# js220_evk1.net
KiCad netlist of a schematic drawn in EAGLE
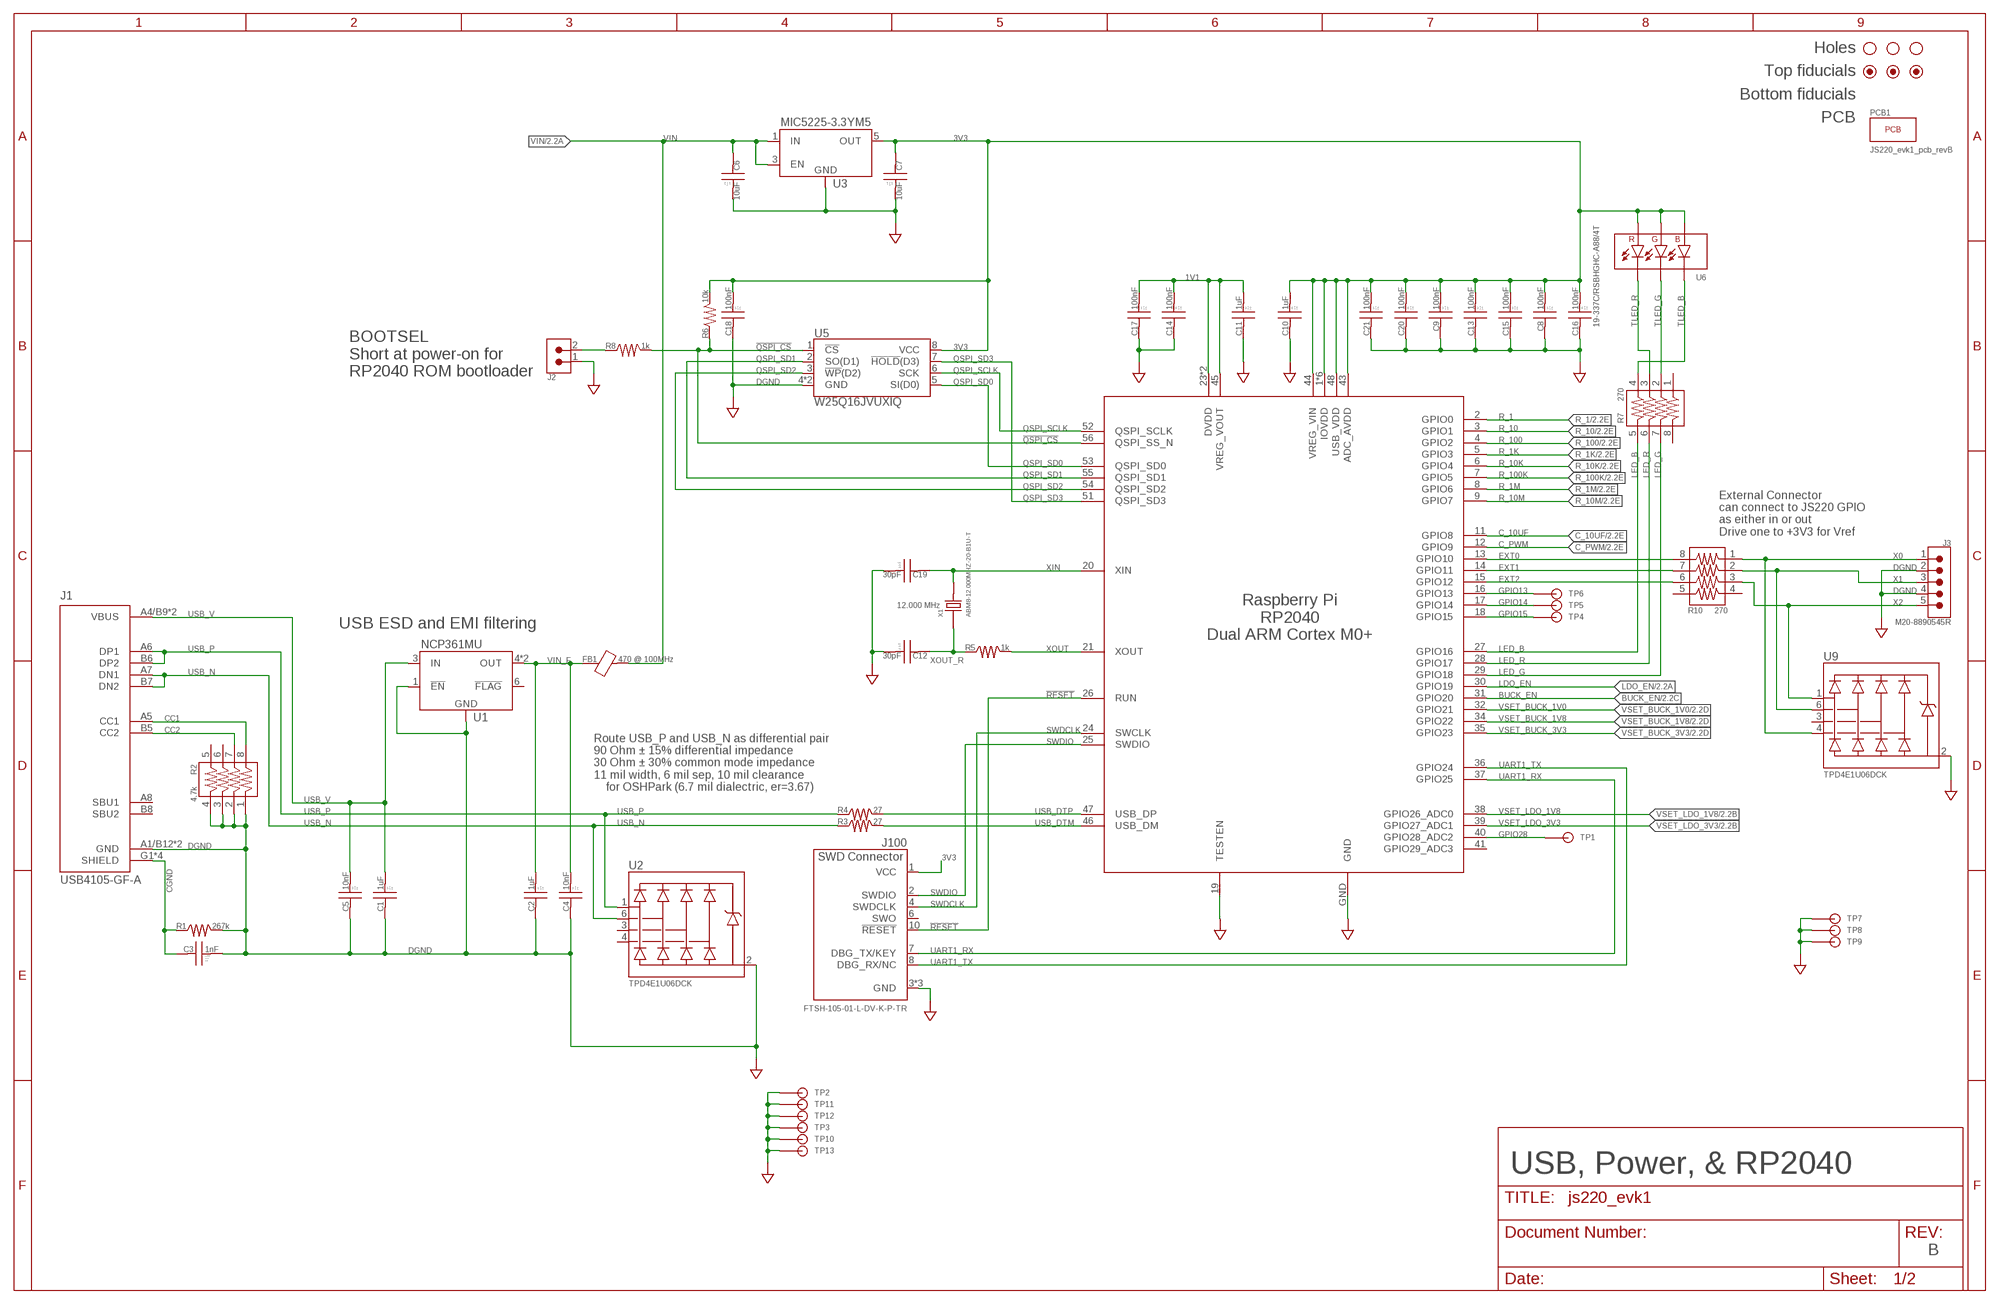
[diagram p0: schematic, sheet 1]
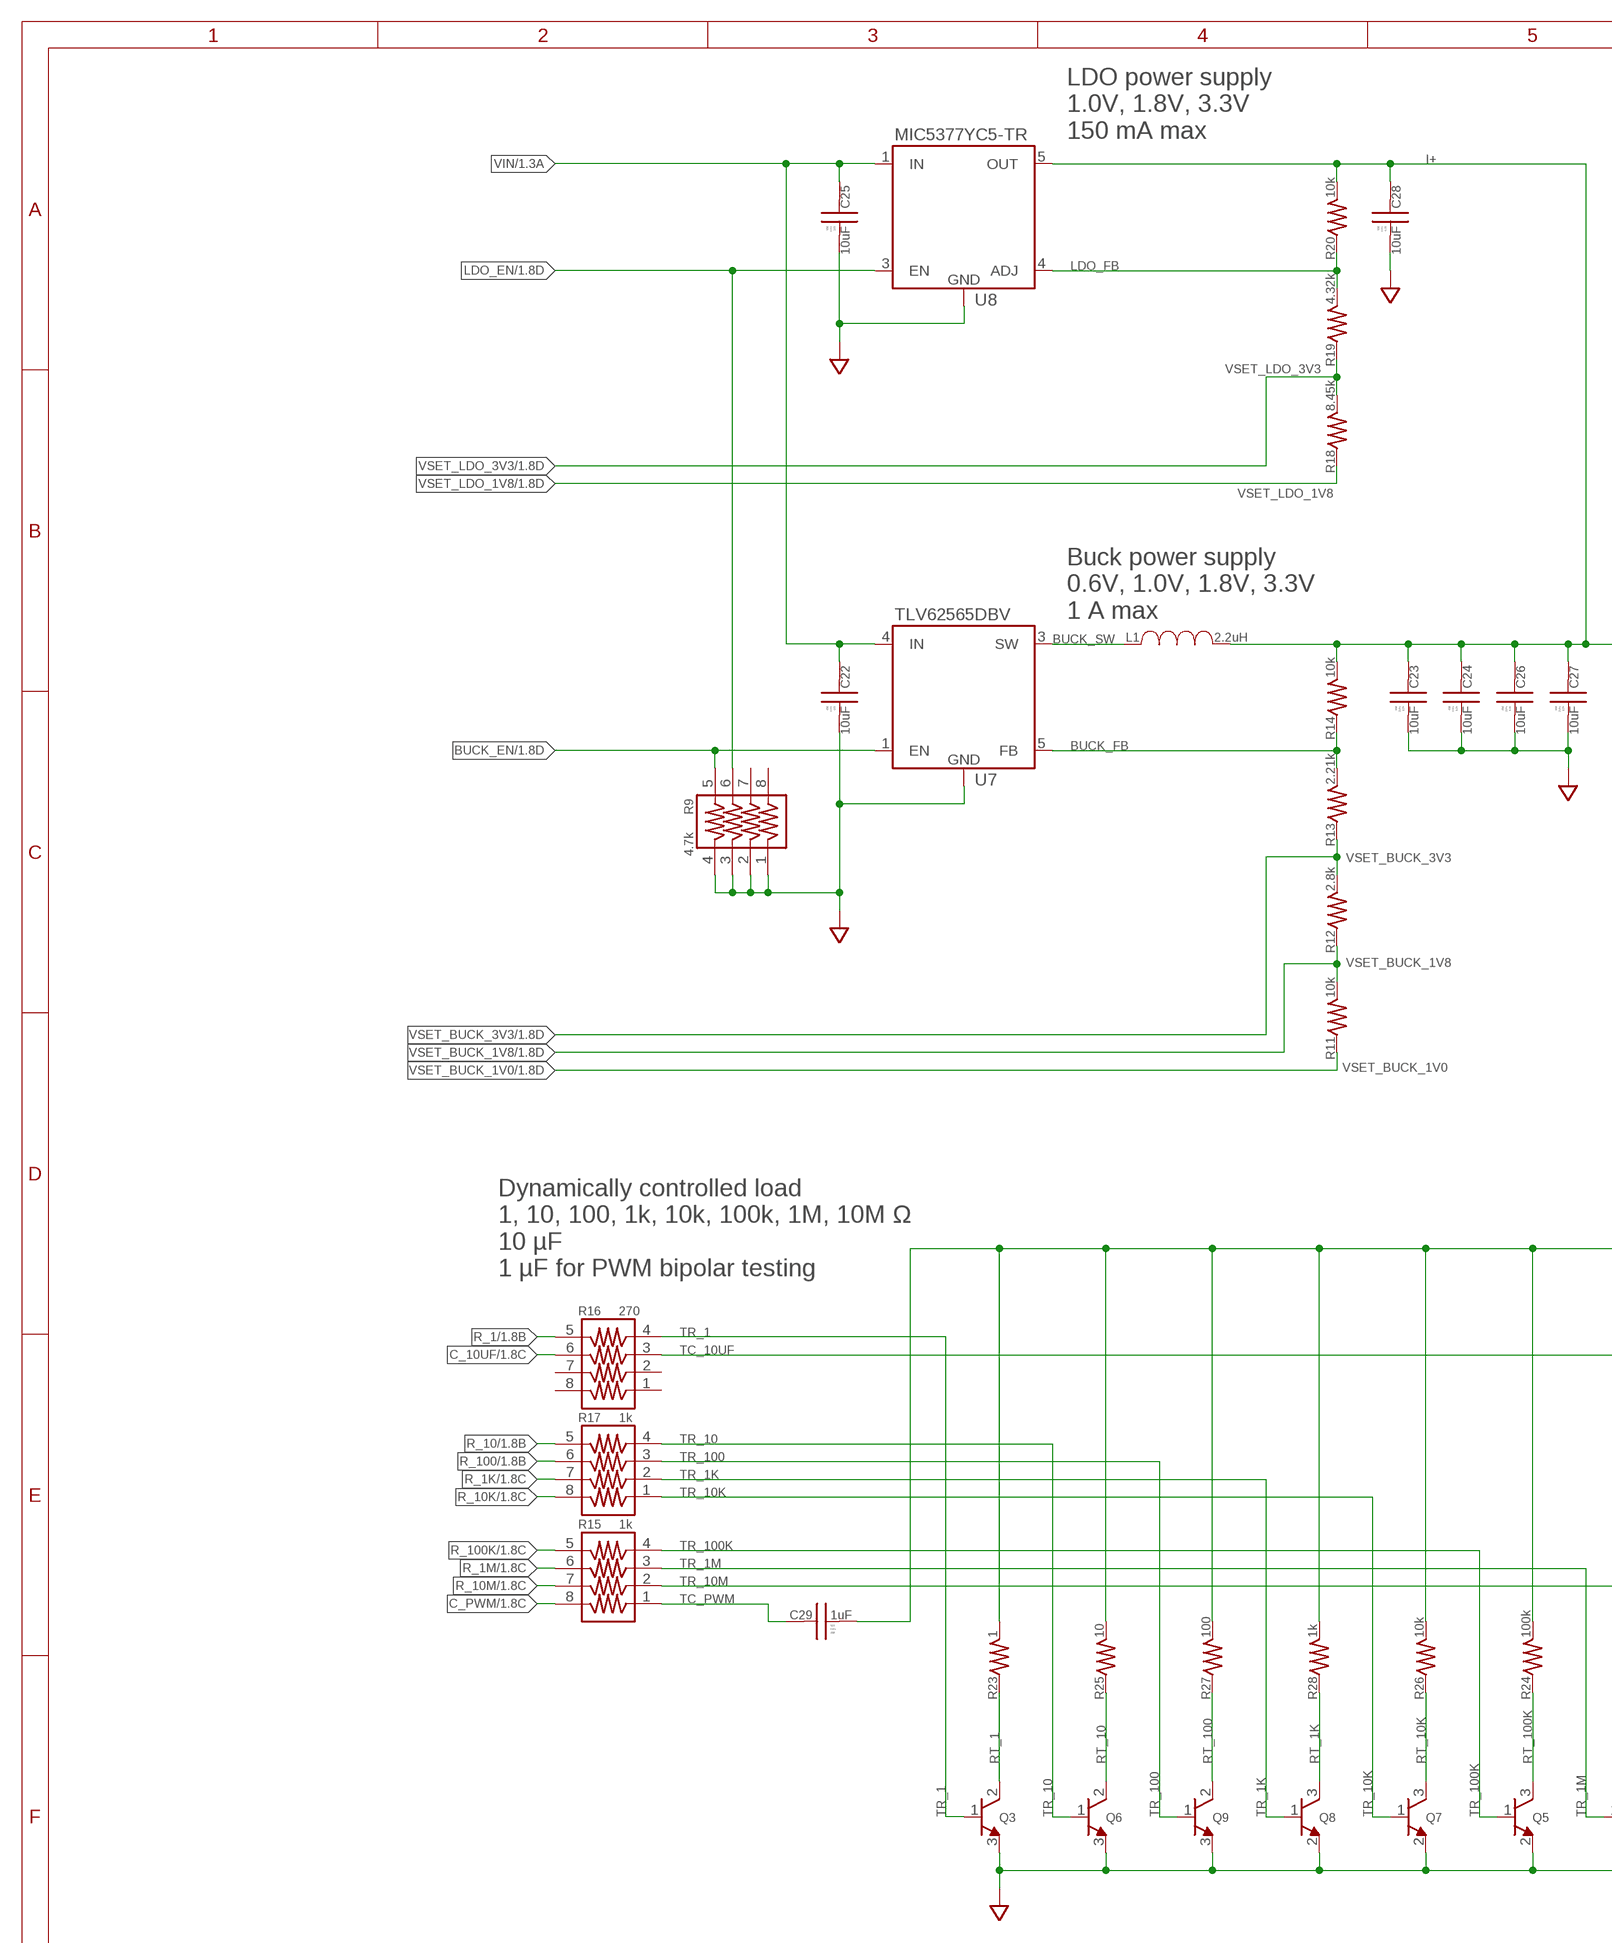
[diagram p1: schematic, sheet 2, part 1 of 2]
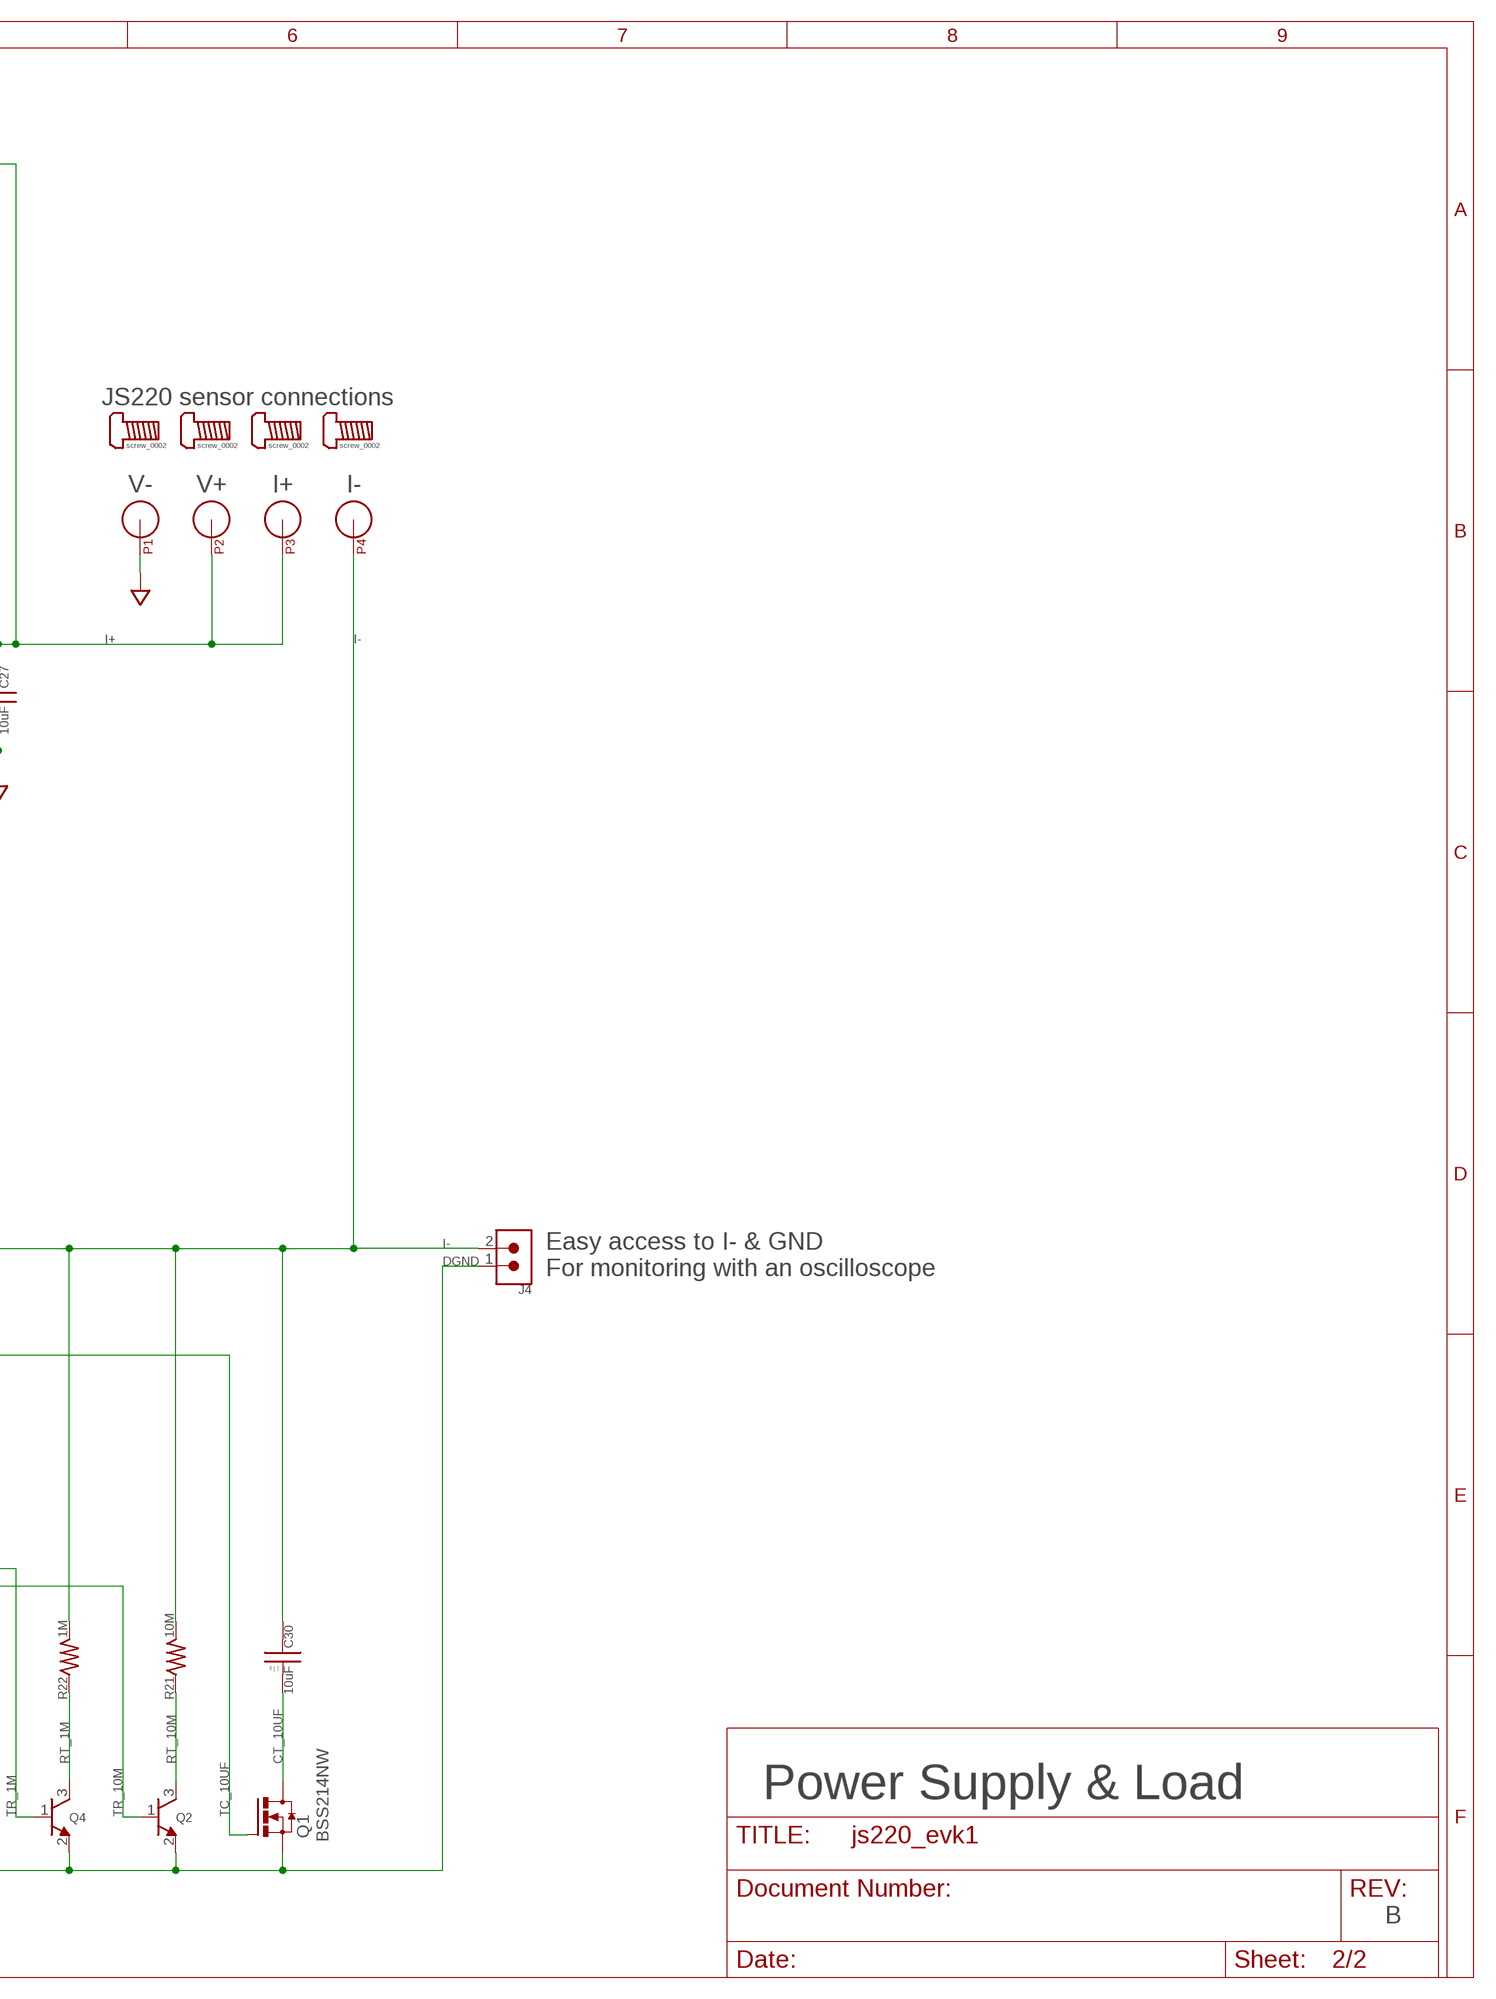
[diagram p2: schematic, sheet 2, part 2 of 2]

(export (version "E")
  (design (tool "Eeschema 10.0.6"))
  (components
    (comp (ref "C1")
      (value "1uF")
      (footprint "eagle-import:0603")
      (fields
        (field (name "DIELECTRIC") "X5R")
        (field (name "TOLERANCE") "20%")
        (field (name "VOLTAGE") "50V")
      )
      (libsource (lib "eagle-import") (part "CAP_0603"))
    )
    (comp (ref "C2")
      (value "1uF")
      (footprint "eagle-import:0603")
      (fields
        (field (name "DIELECTRIC") "X5R")
        (field (name "TOLERANCE") "20%")
        (field (name "VOLTAGE") "50V")
      )
      (libsource (lib "eagle-import") (part "CAP_0603"))
    )
    (comp (ref "C3")
      (value "1nF")
      (footprint "eagle-import:0805")
      (fields
        (field (name "DIELECTRIC") "X5R")
        (field (name "TOLERANCE") "20%")
        (field (name "VOLTAGE") "1000V")
      )
      (libsource (lib "eagle-import") (part "CAP_0805"))
    )
    (comp (ref "C4")
      (value "10nF")
      (footprint "eagle-import:0402")
      (fields
        (field (name "DIELECTRIC") "X7R")
        (field (name "TOLERANCE") "10%")
        (field (name "VOLTAGE") "50V")
      )
      (libsource (lib "eagle-import") (part "CAP_0402"))
    )
    (comp (ref "C5")
      (value "10nF")
      (footprint "eagle-import:0402")
      (fields
        (field (name "DIELECTRIC") "X7R")
        (field (name "TOLERANCE") "10%")
        (field (name "VOLTAGE") "50V")
      )
      (libsource (lib "eagle-import") (part "CAP_0402"))
    )
    (comp (ref "C6")
      (value "10uF")
      (footprint "eagle-import:1206")
      (fields
        (field (name "DIELECTRIC") "X5R")
        (field (name "TOLERANCE") "20%")
        (field (name "VOLTAGE") "10V")
      )
      (libsource (lib "eagle-import") (part "CAP_1206"))
    )
    (comp (ref "C7")
      (value "10uF")
      (footprint "eagle-import:0805")
      (fields
        (field (name "DIELECTRIC") "X5R")
        (field (name "TOLERANCE") "20%")
        (field (name "VOLTAGE") "6.3V")
      )
      (libsource (lib "eagle-import") (part "CAP_0805"))
    )
    (comp (ref "C8")
      (value "100nF")
      (footprint "eagle-import:0402")
      (fields
        (field (name "DIELECTRIC") "X7R")
        (field (name "TOLERANCE") "10%")
        (field (name "VOLTAGE") "50V")
      )
      (libsource (lib "eagle-import") (part "CAP_0402"))
    )
    (comp (ref "C9")
      (value "100nF")
      (footprint "eagle-import:0402")
      (fields
        (field (name "DIELECTRIC") "X7R")
        (field (name "TOLERANCE") "10%")
        (field (name "VOLTAGE") "50V")
      )
      (libsource (lib "eagle-import") (part "CAP_0402"))
    )
    (comp (ref "C10")
      (value "1uF")
      (footprint "eagle-import:0603")
      (fields
        (field (name "DIELECTRIC") "X5R")
        (field (name "TOLERANCE") "20%")
        (field (name "VOLTAGE") "50V")
      )
      (libsource (lib "eagle-import") (part "CAP_0603"))
    )
    (comp (ref "C11")
      (value "1uF")
      (footprint "eagle-import:0603")
      (fields
        (field (name "DIELECTRIC") "X5R")
        (field (name "TOLERANCE") "20%")
        (field (name "VOLTAGE") "50V")
      )
      (libsource (lib "eagle-import") (part "CAP_0603"))
    )
    (comp (ref "C12")
      (value "30pF")
      (footprint "eagle-import:0402")
      (fields
        (field (name "DIELECTRIC") "C0G")
        (field (name "TOLERANCE") "5%")
        (field (name "VOLTAGE") "50V")
      )
      (libsource (lib "eagle-import") (part "CAP_0402"))
    )
    (comp (ref "C13")
      (value "100nF")
      (footprint "eagle-import:0402")
      (fields
        (field (name "DIELECTRIC") "X7R")
        (field (name "TOLERANCE") "10%")
        (field (name "VOLTAGE") "50V")
      )
      (libsource (lib "eagle-import") (part "CAP_0402"))
    )
    (comp (ref "C14")
      (value "100nF")
      (footprint "eagle-import:0402")
      (fields
        (field (name "DIELECTRIC") "X7R")
        (field (name "TOLERANCE") "10%")
        (field (name "VOLTAGE") "50V")
      )
      (libsource (lib "eagle-import") (part "CAP_0402"))
    )
    (comp (ref "C15")
      (value "100nF")
      (footprint "eagle-import:0402")
      (fields
        (field (name "DIELECTRIC") "X7R")
        (field (name "TOLERANCE") "10%")
        (field (name "VOLTAGE") "50V")
      )
      (libsource (lib "eagle-import") (part "CAP_0402"))
    )
    (comp (ref "C16")
      (value "100nF")
      (footprint "eagle-import:0402")
      (fields
        (field (name "DIELECTRIC") "X7R")
        (field (name "TOLERANCE") "10%")
        (field (name "VOLTAGE") "50V")
      )
      (libsource (lib "eagle-import") (part "CAP_0402"))
    )
    (comp (ref "C17")
      (value "100nF")
      (footprint "eagle-import:0402")
      (fields
        (field (name "DIELECTRIC") "X7R")
        (field (name "TOLERANCE") "10%")
        (field (name "VOLTAGE") "50V")
      )
      (libsource (lib "eagle-import") (part "CAP_0402"))
    )
    (comp (ref "C18")
      (value "100nF")
      (footprint "eagle-import:0402")
      (fields
        (field (name "DIELECTRIC") "X7R")
        (field (name "TOLERANCE") "10%")
        (field (name "VOLTAGE") "50V")
      )
      (libsource (lib "eagle-import") (part "CAP_0402"))
    )
    (comp (ref "C19")
      (value "30pF")
      (footprint "eagle-import:0402")
      (fields
        (field (name "DIELECTRIC") "C0G")
        (field (name "TOLERANCE") "5%")
        (field (name "VOLTAGE") "50V")
      )
      (libsource (lib "eagle-import") (part "CAP_0402"))
    )
    (comp (ref "C20")
      (value "100nF")
      (footprint "eagle-import:0402")
      (fields
        (field (name "DIELECTRIC") "X7R")
        (field (name "TOLERANCE") "10%")
        (field (name "VOLTAGE") "50V")
      )
      (libsource (lib "eagle-import") (part "CAP_0402"))
    )
    (comp (ref "C21")
      (value "100nF")
      (footprint "eagle-import:0402")
      (fields
        (field (name "DIELECTRIC") "X7R")
        (field (name "TOLERANCE") "10%")
        (field (name "VOLTAGE") "50V")
      )
      (libsource (lib "eagle-import") (part "CAP_0402"))
    )
    (comp (ref "FB1")
      (value "470 @ 100MHz")
      (footprint "eagle-import:0603")
      (libsource (lib "eagle-import") (part "FERRITE_BEAD_0603"))
    )
    (comp (ref "FD1")
      (value "DNI")
      (footprint "eagle-import:FIDUCIAL_1MM_2MM")
      (libsource (lib "eagle-import") (part "FIDUCIAL_1MM"))
    )
    (comp (ref "FD2")
      (value "DNI")
      (footprint "eagle-import:FIDUCIAL_1MM_2MM")
      (libsource (lib "eagle-import") (part "FIDUCIAL_1MM"))
    )
    (comp (ref "FD3")
      (value "DNI")
      (footprint "eagle-import:FIDUCIAL_1MM_2MM")
      (libsource (lib "eagle-import") (part "FIDUCIAL_1MM"))
    )
    (comp (ref "H1")
      (value "STAND-OFFTIGHT")
      (footprint "eagle-import:STAND-OFF-TIGHT")
      (libsource (lib "eagle-import") (part "STAND-OFFTIGHT"))
    )
    (comp (ref "H2")
      (value "STAND-OFFTIGHT")
      (footprint "eagle-import:STAND-OFF-TIGHT")
      (libsource (lib "eagle-import") (part "STAND-OFFTIGHT"))
    )
    (comp (ref "H3")
      (value "STAND-OFFTIGHT")
      (footprint "eagle-import:STAND-OFF-TIGHT")
      (libsource (lib "eagle-import") (part "STAND-OFFTIGHT"))
    )
    (comp (ref "J1")
      (value "USB4105-GF-A")
      (footprint "eagle-import:GCT_USB4105_REVA")
      (fields
        (field (name "DIGI-KEY_PART_NUMBER") "2073-USB4105-GF-ACT-ND")
        (field (name "MF") "Global Connector Technology")
        (field (name "MP") "USB4105")
      )
      (libsource (lib "eagle-import") (part "USB4105_REVA"))
    )
    (comp (ref "J2")
      (value "CONN_0.1_2X1")
      (footprint "eagle-import:CONN_0.1_2X1_M")
      (libsource (lib "eagle-import") (part "CONN_0.1_2X1"))
    )
    (comp (ref "J3")
      (value "M20-8890545R")
      (footprint "eagle-import:CONN_0.1_5X1_MSR")
      (libsource (lib "eagle-import") (part "CONN_0.1_5X1_MSR"))
    )
    (comp (ref "J100")
      (value "FTSH-105-01-L-DV-K-P-TR")
      (footprint "eagle-import:CONN_0.050_5X2_M_SM")
      (libsource (lib "eagle-import") (part "ARM_SWD_10_0.05_2X10_S"))
    )
    (comp (ref "R1")
      (value "267k")
      (footprint "eagle-import:0402")
      (fields
        (field (name "TEMP_CO") "100 ppm/°C")
        (field (name "TOLERANCE") "1%")
        (field (name "WATTAGE") "0.062W")
      )
      (libsource (lib "eagle-import") (part "RESISTOR_0402"))
    )
    (comp (ref "R2")
      (value "4.7k")
      (footprint "eagle-import:0402X4")
      (fields (field (name "TOLERANCE") "5%"))
      (libsource (lib "eagle-import") (part "RESISTOR_4_0804"))
    )
    (comp (ref "R3")
      (value "27")
      (footprint "eagle-import:0402")
      (fields
        (field (name "TEMP_CO") "100 ppm/°C")
        (field (name "TOLERANCE") "1%")
        (field (name "WATTAGE") "0.062W")
      )
      (libsource (lib "eagle-import") (part "RESISTOR_0402"))
    )
    (comp (ref "R4")
      (value "27")
      (footprint "eagle-import:0402")
      (fields
        (field (name "TEMP_CO") "100 ppm/°C")
        (field (name "TOLERANCE") "1%")
        (field (name "WATTAGE") "0.062W")
      )
      (libsource (lib "eagle-import") (part "RESISTOR_0402"))
    )
    (comp (ref "R5")
      (value "1k")
      (footprint "eagle-import:0402")
      (fields
        (field (name "TEMP_CO") "25 ppm/°C")
        (field (name "TOLERANCE") "0.1%")
        (field (name "WATTAGE") "0.062W")
      )
      (libsource (lib "eagle-import") (part "RESISTOR_0402"))
    )
    (comp (ref "R6")
      (value "10k")
      (footprint "eagle-import:0402")
      (fields
        (field (name "TEMP_CO") "25 ppm/°C")
        (field (name "TOLERANCE") "0.1%")
        (field (name "WATTAGE") "0.062W")
      )
      (libsource (lib "eagle-import") (part "RESISTOR_0402"))
    )
    (comp (ref "R7")
      (value "270")
      (footprint "eagle-import:0402X4")
      (fields (field (name "TOLERANCE") "5%"))
      (libsource (lib "eagle-import") (part "RESISTOR_4_0804"))
    )
    (comp (ref "R8")
      (value "1k")
      (footprint "eagle-import:0402")
      (fields
        (field (name "TEMP_CO") "25 ppm/°C")
        (field (name "TOLERANCE") "0.1%")
        (field (name "WATTAGE") "0.062W")
      )
      (libsource (lib "eagle-import") (part "RESISTOR_0402"))
    )
    (comp (ref "R10")
      (value "270")
      (footprint "eagle-import:0402X4")
      (fields (field (name "TOLERANCE") "5%"))
      (libsource (lib "eagle-import") (part "RESISTOR_4_0804"))
    )
    (comp (ref "TP1")
      (value "TPTP-PTH0.02")
      (footprint "eagle-import:TP-PTH0.02")
      (libsource (lib "eagle-import") (part "TPTP-PTH0.02"))
    )
    (comp (ref "TP2")
      (value "TPTP-PTH0.02")
      (footprint "eagle-import:TP-PTH0.02")
      (libsource (lib "eagle-import") (part "TPTP-PTH0.02"))
    )
    (comp (ref "TP3")
      (value "TPTP-PTH0.02")
      (footprint "eagle-import:TP-PTH0.02")
      (libsource (lib "eagle-import") (part "TPTP-PTH0.02"))
    )
    (comp (ref "TP4")
      (value "TPTP-PTH0.02")
      (footprint "eagle-import:TP-PTH0.02")
      (libsource (lib "eagle-import") (part "TPTP-PTH0.02"))
    )
    (comp (ref "TP5")
      (value "TPTP-PTH0.02")
      (footprint "eagle-import:TP-PTH0.02")
      (libsource (lib "eagle-import") (part "TPTP-PTH0.02"))
    )
    (comp (ref "TP6")
      (value "TPTP-PTH0.02")
      (footprint "eagle-import:TP-PTH0.02")
      (libsource (lib "eagle-import") (part "TPTP-PTH0.02"))
    )
    (comp (ref "TP7")
      (value "TPTP-PTH0.02")
      (footprint "eagle-import:TP-PTH0.02")
      (libsource (lib "eagle-import") (part "TPTP-PTH0.02"))
    )
    (comp (ref "TP8")
      (value "TPTP-PTH0.02")
      (footprint "eagle-import:TP-PTH0.02")
      (libsource (lib "eagle-import") (part "TPTP-PTH0.02"))
    )
    (comp (ref "TP9")
      (value "TPTP-PTH0.02")
      (footprint "eagle-import:TP-PTH0.02")
      (libsource (lib "eagle-import") (part "TPTP-PTH0.02"))
    )
    (comp (ref "TP10")
      (value "TPTP-PTH0.02")
      (footprint "eagle-import:TP-PTH0.02")
      (libsource (lib "eagle-import") (part "TPTP-PTH0.02"))
    )
    (comp (ref "TP11")
      (value "TPTP-PTH0.02")
      (footprint "eagle-import:TP-PTH0.02")
      (libsource (lib "eagle-import") (part "TPTP-PTH0.02"))
    )
    (comp (ref "TP12")
      (value "TPTP-PTH0.02")
      (footprint "eagle-import:TP-PTH0.02")
      (libsource (lib "eagle-import") (part "TPTP-PTH0.02"))
    )
    (comp (ref "TP13")
      (value "TPTP-PTH0.02")
      (footprint "eagle-import:TP-PTH0.02")
      (libsource (lib "eagle-import") (part "TPTP-PTH0.02"))
    )
    (comp (ref "U1")
      (value "NCP361MU")
      (footprint "eagle-import:UDFN-6")
      (fields (field (name "MPN") "NCP361MUTBG"))
      (libsource (lib "eagle-import") (part "NCP361MU"))
    )
    (comp (ref "U2")
      (value "TPD4E1U06DCK")
      (footprint "eagle-import:SC-70-6")
      (libsource (lib "eagle-import") (part "TVS_4UNI_DCK"))
    )
    (comp (ref "U3")
      (value "MIC5225-3.3YM5")
      (footprint "eagle-import:SOT23-5")
      (fields (field (name "MPN") "MIC5225-3.3YM5-TR"))
      (libsource (lib "eagle-import") (part "VREG_FIXED+_ENTPS70960DBV"))
    )
    (comp (ref "U4")
      (value "RP2040")
      (footprint "eagle-import:QFN-56G")
      (libsource (lib "eagle-import") (part "RP2040"))
    )
    (comp (ref "U5")
      (value "W25Q16JVUXIQ")
      (footprint "eagle-import:USON-8_2X3")
      (fields (field (name "MPN") "W25Q16JVUXIQ TR"))
      (libsource (lib "eagle-import") (part "FLASH_SERIAL8_USON8_2X3"))
    )
    (comp (ref "U6")
      (value "19-337C/RSBHGHC-A88/4T")
      (footprint "eagle-import:LED_RGB6_1.6X1.6")
      (libsource (lib "eagle-import") (part "LED_RGB6_1.6X1.6"))
    )
    (comp (ref "U9")
      (value "TPD4E1U06DCK")
      (footprint "eagle-import:SC-70-6")
      (libsource (lib "eagle-import") (part "TVS_4UNI_DCK"))
    )
    (comp (ref "X1")
      (value "ABM8-12.000MHZ-20-B1U-T")
      (footprint "eagle-import:XTAL4_3.2X2.5")
      (libsource (lib "eagle-import") (part "XTAL-2_XTAL4_3.2X2.5"))
    )
    (comp (ref "C22")
      (value "10uF")
      (footprint "eagle-import:1206")
      (fields
        (field (name "DIELECTRIC") "X5R")
        (field (name "TOLERANCE") "20%")
        (field (name "VOLTAGE") "10V")
      )
      (libsource (lib "eagle-import") (part "CAP_1206"))
    )
    (comp (ref "C23")
      (value "10uF")
      (footprint "eagle-import:0805")
      (fields
        (field (name "DIELECTRIC") "X5R")
        (field (name "TOLERANCE") "20%")
        (field (name "VOLTAGE") "6.3V")
      )
      (libsource (lib "eagle-import") (part "CAP_0805"))
    )
    (comp (ref "C24")
      (value "10uF")
      (footprint "eagle-import:0805")
      (fields
        (field (name "DIELECTRIC") "X5R")
        (field (name "TOLERANCE") "20%")
        (field (name "VOLTAGE") "6.3V")
      )
      (libsource (lib "eagle-import") (part "CAP_0805"))
    )
    (comp (ref "C25")
      (value "10uF")
      (footprint "eagle-import:1206")
      (fields
        (field (name "DIELECTRIC") "X5R")
        (field (name "TOLERANCE") "20%")
        (field (name "VOLTAGE") "10V")
      )
      (libsource (lib "eagle-import") (part "CAP_1206"))
    )
    (comp (ref "C26")
      (value "10uF")
      (footprint "eagle-import:0805")
      (fields
        (field (name "DIELECTRIC") "X5R")
        (field (name "TOLERANCE") "20%")
        (field (name "VOLTAGE") "6.3V")
      )
      (libsource (lib "eagle-import") (part "CAP_0805"))
    )
    (comp (ref "C27")
      (value "10uF")
      (footprint "eagle-import:0805")
      (fields
        (field (name "DIELECTRIC") "X5R")
        (field (name "TOLERANCE") "20%")
        (field (name "VOLTAGE") "6.3V")
      )
      (libsource (lib "eagle-import") (part "CAP_0805"))
    )
    (comp (ref "C28")
      (value "10uF")
      (footprint "eagle-import:0805")
      (fields
        (field (name "DIELECTRIC") "X5R")
        (field (name "TOLERANCE") "20%")
        (field (name "VOLTAGE") "6.3V")
      )
      (libsource (lib "eagle-import") (part "CAP_0805"))
    )
    (comp (ref "C29")
      (value "1uF")
      (footprint "eagle-import:0603")
      (fields
        (field (name "DIELECTRIC") "X5R")
        (field (name "TOLERANCE") "20%")
        (field (name "VOLTAGE") "50V")
      )
      (libsource (lib "eagle-import") (part "CAP_0603"))
    )
    (comp (ref "C30")
      (value "10uF")
      (footprint "eagle-import:0805")
      (fields
        (field (name "DIELECTRIC") "X5R")
        (field (name "TOLERANCE") "20%")
        (field (name "VOLTAGE") "6.3V")
      )
      (libsource (lib "eagle-import") (part "CAP_0805"))
    )
    (comp (ref "J4")
      (value "CONN_0.1_2X1")
      (footprint "eagle-import:CONN_0.1_2X1_M")
      (libsource (lib "eagle-import") (part "CONN_0.1_2X1"))
    )
    (comp (ref "L1")
      (value "2.2uH")
      (footprint "eagle-import:LPS4018")
      (fields (field (name "MPN") "NRS4018T2R2MDGJ"))
      (libsource (lib "eagle-import") (part "INDUCTOR_LPS4018"))
    )
    (comp (ref "P1")
      (value "P55-271F40N")
      (footprint "eagle-import:72918")
      (libsource (lib "eagle-import") (part "BANANA-PLUG72918"))
    )
    (comp (ref "P2")
      (value "P55-271F40N")
      (footprint "eagle-import:72918")
      (libsource (lib "eagle-import") (part "BANANA-PLUG72918"))
    )
    (comp (ref "P3")
      (value "P55-271F40N")
      (footprint "eagle-import:72918")
      (libsource (lib "eagle-import") (part "BANANA-PLUG72918"))
    )
    (comp (ref "P4")
      (value "P55-271F40N")
      (footprint "eagle-import:72918")
      (libsource (lib "eagle-import") (part "BANANA-PLUG72918"))
    )
    (comp (ref "Q1")
      (value "BSS214NW")
      (footprint "eagle-import:SOT323-3")
      (fields (field (name "MPN") "BSS214NWH6327XTSA1"))
      (libsource (lib "eagle-import") (part "MOSFET_N_SOT323_GSD"))
    )
    (comp (ref "Q2")
      (value "BC848W")
      (footprint "eagle-import:SOT323-3")
      (libsource (lib "eagle-import") (part "BJT_NPN_SOT323"))
    )
    (comp (ref "Q3")
      (value "PBSS4240X")
      (footprint "eagle-import:SOT-89")
      (libsource (lib "eagle-import") (part "BJT_NPN_SOT89"))
    )
    (comp (ref "Q4")
      (value "BC848W")
      (footprint "eagle-import:SOT323-3")
      (libsource (lib "eagle-import") (part "BJT_NPN_SOT323"))
    )
    (comp (ref "Q5")
      (value "BC848W")
      (footprint "eagle-import:SOT323-3")
      (libsource (lib "eagle-import") (part "BJT_NPN_SOT323"))
    )
    (comp (ref "Q6")
      (value "PBSS4240X")
      (footprint "eagle-import:SOT-89")
      (libsource (lib "eagle-import") (part "BJT_NPN_SOT89"))
    )
    (comp (ref "Q7")
      (value "BC848W")
      (footprint "eagle-import:SOT323-3")
      (libsource (lib "eagle-import") (part "BJT_NPN_SOT323"))
    )
    (comp (ref "Q8")
      (value "BC848W")
      (footprint "eagle-import:SOT323-3")
      (libsource (lib "eagle-import") (part "BJT_NPN_SOT323"))
    )
    (comp (ref "Q9")
      (value "PBSS4240X")
      (footprint "eagle-import:SOT-89")
      (libsource (lib "eagle-import") (part "BJT_NPN_SOT89"))
    )
    (comp (ref "R9")
      (value "4.7k")
      (footprint "eagle-import:0402X4")
      (fields (field (name "TOLERANCE") "5%"))
      (libsource (lib "eagle-import") (part "RESISTOR_4_0804"))
    )
    (comp (ref "R11")
      (value "10k")
      (footprint "eagle-import:0402")
      (fields
        (field (name "TEMP_CO") "25 ppm/°C")
        (field (name "TOLERANCE") "0.1%")
        (field (name "WATTAGE") "0.062W")
      )
      (libsource (lib "eagle-import") (part "RESISTOR_0402"))
    )
    (comp (ref "R12")
      (value "2.8k")
      (footprint "eagle-import:0402")
      (fields
        (field (name "TEMP_CO") "25 ppm/°C")
        (field (name "TOLERANCE") "0.1%")
        (field (name "WATTAGE") "0.062W")
      )
      (libsource (lib "eagle-import") (part "RESISTOR_0402"))
    )
    (comp (ref "R13")
      (value "2.21k")
      (footprint "eagle-import:0402")
      (fields
        (field (name "TEMP_CO") "25 ppm/°C")
        (field (name "TOLERANCE") "0.1%")
        (field (name "WATTAGE") "0.062W")
      )
      (libsource (lib "eagle-import") (part "RESISTOR_0402"))
    )
    (comp (ref "R14")
      (value "10k")
      (footprint "eagle-import:0402")
      (fields
        (field (name "TEMP_CO") "25 ppm/°C")
        (field (name "TOLERANCE") "0.1%")
        (field (name "WATTAGE") "0.062W")
      )
      (libsource (lib "eagle-import") (part "RESISTOR_0402"))
    )
    (comp (ref "R15")
      (value "1k")
      (footprint "eagle-import:0402X4")
      (fields (field (name "TOLERANCE") "5%"))
      (libsource (lib "eagle-import") (part "RESISTOR_4_0804"))
    )
    (comp (ref "R16")
      (value "270")
      (footprint "eagle-import:0402X4")
      (fields (field (name "TOLERANCE") "5%"))
      (libsource (lib "eagle-import") (part "RESISTOR_4_0804"))
    )
    (comp (ref "R17")
      (value "1k")
      (footprint "eagle-import:0402X4")
      (fields (field (name "TOLERANCE") "5%"))
      (libsource (lib "eagle-import") (part "RESISTOR_4_0804"))
    )
    (comp (ref "R18")
      (value "8.45k")
      (footprint "eagle-import:0402")
      (fields
        (field (name "TEMP_CO") "25 ppm/°C")
        (field (name "TOLERANCE") "1%")
        (field (name "WATTAGE") "0.062W")
      )
      (libsource (lib "eagle-import") (part "RESISTOR_0402"))
    )
    (comp (ref "R19")
      (value "4.32k")
      (footprint "eagle-import:0402")
      (fields
        (field (name "TEMP_CO") "25 ppm/°C")
        (field (name "TOLERANCE") "1%")
        (field (name "WATTAGE") "0.062W")
      )
      (libsource (lib "eagle-import") (part "RESISTOR_0402"))
    )
    (comp (ref "R20")
      (value "10k")
      (footprint "eagle-import:0402")
      (fields
        (field (name "TEMP_CO") "25 ppm/°C")
        (field (name "TOLERANCE") "0.1%")
        (field (name "WATTAGE") "0.062W")
      )
      (libsource (lib "eagle-import") (part "RESISTOR_0402"))
    )
    (comp (ref "R21")
      (value "10M")
      (footprint "eagle-import:0402")
      (fields
        (field (name "TEMP_CO") "100 ppm/°C")
        (field (name "TOLERANCE") "1%")
        (field (name "WATTAGE") "0.062W")
      )
      (libsource (lib "eagle-import") (part "RESISTOR_0402"))
    )
    (comp (ref "R22")
      (value "1M")
      (footprint "eagle-import:0402")
      (fields
        (field (name "TEMP_CO") "100 ppm/°C")
        (field (name "TOLERANCE") "1%")
        (field (name "WATTAGE") "0.062W")
      )
      (libsource (lib "eagle-import") (part "RESISTOR_0402"))
    )
    (comp (ref "R23")
      (value "1")
      (footprint "eagle-import:2512")
      (fields
        (field (name "TEMP_CO") "100 ppm/°C")
        (field (name "TOLERANCE") "1%")
        (field (name "WATTAGE") "2W")
      )
      (libsource (lib "eagle-import") (part "RESISTOR_2512"))
    )
    (comp (ref "R24")
      (value "100k")
      (footprint "eagle-import:0402")
      (fields
        (field (name "TEMP_CO") "25 ppm/°C")
        (field (name "TOLERANCE") "0.1%")
        (field (name "WATTAGE") "0.062W")
      )
      (libsource (lib "eagle-import") (part "RESISTOR_0402"))
    )
    (comp (ref "R25")
      (value "10")
      (footprint "eagle-import:2512")
      (fields
        (field (name "TEMP_CO") "100 ppm/°C")
        (field (name "TOLERANCE") "1%")
        (field (name "WATTAGE") "2W")
      )
      (libsource (lib "eagle-import") (part "RESISTOR_2512"))
    )
    (comp (ref "R26")
      (value "10k")
      (footprint "eagle-import:0402")
      (fields
        (field (name "TEMP_CO") "25 ppm/°C")
        (field (name "TOLERANCE") "0.1%")
        (field (name "WATTAGE") "0.062W")
      )
      (libsource (lib "eagle-import") (part "RESISTOR_0402"))
    )
    (comp (ref "R27")
      (value "100")
      (footprint "eagle-import:1206")
      (fields
        (field (name "TEMP_CO") "100 ppm/°C")
        (field (name "TOLERANCE") "1%")
        (field (name "WATTAGE") "0.5W")
      )
      (libsource (lib "eagle-import") (part "RESISTOR_1206"))
    )
    (comp (ref "R28")
      (value "1k")
      (footprint "eagle-import:0402")
      (fields
        (field (name "TEMP_CO") "25 ppm/°C")
        (field (name "TOLERANCE") "0.1%")
        (field (name "WATTAGE") "0.062W")
      )
      (libsource (lib "eagle-import") (part "RESISTOR_0402"))
    )
    (comp (ref "U7")
      (value "TLV62565DBV")
      (footprint "eagle-import:SOT23-5")
      (libsource (lib "eagle-import") (part "TLV62565DBV"))
    )
    (comp (ref "U8")
      (value "MIC5377YC5-TR")
      (footprint "eagle-import:SC-70-5")
      (fields (field (name "MPN") "MIC5377YC5-TR"))
      (libsource (lib "eagle-import") (part "VREG+_FB_EN_MIC5376-YC5"))
    )
  )
  (nets
    (net (code "1") (name "1V1") (class "Default")
      (node (ref "C11") (pin "2") (pinfunction "2_2") (pintype "bidirectional"))
      (node (ref "C14") (pin "2") (pinfunction "2_2") (pintype "bidirectional"))
      (node (ref "C17") (pin "2") (pinfunction "2_2") (pintype "bidirectional"))
      (node (ref "U4") (pin "23") (pinfunction "DVDD_23") (pintype "bidirectional"))
      (node (ref "U4") (pin "45") (pinfunction "VREG_VOUT_45") (pintype "bidirectional"))
      (node (ref "U4") (pin "50") (pinfunction "DVDD_50") (pintype "bidirectional"))
    )
    (net (code "2") (name "3V3") (class "Default")
      (node (ref "C10") (pin "2") (pinfunction "2_2") (pintype "bidirectional"))
      (node (ref "C13") (pin "2") (pinfunction "2_2") (pintype "bidirectional"))
      (node (ref "C15") (pin "2") (pinfunction "2_2") (pintype "bidirectional"))
      (node (ref "C16") (pin "2") (pinfunction "2_2") (pintype "bidirectional"))
      (node (ref "C18") (pin "2") (pinfunction "2_2") (pintype "bidirectional"))
      (node (ref "C20") (pin "2") (pinfunction "2_2") (pintype "bidirectional"))
      (node (ref "C21") (pin "2") (pinfunction "2_2") (pintype "bidirectional"))
      (node (ref "C7") (pin "1") (pinfunction "1_1") (pintype "bidirectional"))
      (node (ref "C8") (pin "2") (pinfunction "2_2") (pintype "bidirectional"))
      (node (ref "C9") (pin "2") (pinfunction "2_2") (pintype "bidirectional"))
      (node (ref "J100") (pin "1") (pinfunction "VCC_1") (pintype "bidirectional"))
      (node (ref "R6") (pin "2") (pinfunction "P$2_2") (pintype "bidirectional"))
      (node (ref "U3") (pin "5") (pinfunction "OUT_5") (pintype "bidirectional"))
      (node (ref "U4") (pin "1") (pinfunction "IOVDD_1") (pintype "bidirectional"))
      (node (ref "U4") (pin "10") (pinfunction "IOVDD_10") (pintype "bidirectional"))
      (node (ref "U4") (pin "22") (pinfunction "IOVDD_22") (pintype "bidirectional"))
      (node (ref "U4") (pin "33") (pinfunction "IOVDD_33") (pintype "bidirectional"))
      (node (ref "U4") (pin "42") (pinfunction "IOVDD_42") (pintype "bidirectional"))
      (node (ref "U4") (pin "43") (pinfunction "ADC_AVDD_43") (pintype "bidirectional"))
      (node (ref "U4") (pin "44") (pinfunction "VREG_VIN_44") (pintype "bidirectional"))
      (node (ref "U4") (pin "48") (pinfunction "USB_VDD_48") (pintype "bidirectional"))
      (node (ref "U4") (pin "49") (pinfunction "IOVDD_49") (pintype "bidirectional"))
      (node (ref "U5") (pin "8") (pinfunction "VCC_8") (pintype "bidirectional"))
      (node (ref "U6") (pin "2") (pinfunction "GREEN_ANODE+_2") (pintype "passive"))
      (node (ref "U6") (pin "4") (pinfunction "RED_ANODE+_4") (pintype "passive"))
      (node (ref "U6") (pin "6") (pinfunction "BLUE_ANODE+_6") (pintype "passive"))
    )
    (net (code "3") (name "BUCK_EN") (class "Default")
      (node (ref "R9") (pin "5") (pinfunction "4B_5") (pintype "bidirectional"))
      (node (ref "U4") (pin "31") (pinfunction "GPIO20_31") (pintype "bidirectional"))
      (node (ref "U7") (pin "1") (pinfunction "EN_1") (pintype "bidirectional"))
    )
    (net (code "4") (name "BUCK_FB") (class "Default")
      (node (ref "R13") (pin "2") (pinfunction "P$2_2") (pintype "bidirectional"))
      (node (ref "R14") (pin "1") (pinfunction "P$1_1") (pintype "bidirectional"))
      (node (ref "U7") (pin "5") (pinfunction "FB_5") (pintype "bidirectional"))
    )
    (net (code "5") (name "BUCK_SW") (class "Default")
      (node (ref "L1") (pin "1") (pinfunction "P$1_1") (pintype "bidirectional"))
      (node (ref "U7") (pin "3") (pinfunction "SW_3") (pintype "bidirectional"))
    )
    (net (code "6") (name "CC1") (class "Default")
      (node (ref "J1") (pin "A5") (pinfunction "CC1_A5") (pintype "bidirectional"))
      (node (ref "R2") (pin "8") (pinfunction "1B_8") (pintype "bidirectional"))
    )
    (net (code "7") (name "CC2") (class "Default")
      (node (ref "J1") (pin "B5") (pinfunction "CC2_B5") (pintype "bidirectional"))
      (node (ref "R2") (pin "7") (pinfunction "2B_7") (pintype "bidirectional"))
    )
    (net (code "8") (name "CGND") (class "Default")
      (node (ref "C3") (pin "1") (pinfunction "1_1") (pintype "bidirectional"))
      (node (ref "J1") (pin "G1") (pinfunction "SHIELD_G1") (pintype "power_in"))
      (node (ref "J1") (pin "G2") (pinfunction "SHIELD_G2") (pintype "power_in"))
      (node (ref "J1") (pin "G3") (pinfunction "SHIELD_G3") (pintype "power_in"))
      (node (ref "J1") (pin "G4") (pinfunction "SHIELD_G4") (pintype "power_in"))
      (node (ref "R1") (pin "1") (pinfunction "P$1_1") (pintype "bidirectional"))
    )
    (net (code "9") (name "CT_10UF") (class "Default")
      (node (ref "C30") (pin "2") (pinfunction "2_2") (pintype "bidirectional"))
      (node (ref "Q1") (pin "3") (pinfunction "D_3") (pintype "passive"))
    )
    (net (code "10") (name "C_10UF") (class "Default")
      (node (ref "R16") (pin "6") (pinfunction "3B_6") (pintype "bidirectional"))
      (node (ref "U4") (pin "11") (pinfunction "GPIO8_11") (pintype "bidirectional"))
    )
    (net (code "11") (name "C_PWM") (class "Default")
      (node (ref "R15") (pin "8") (pinfunction "1B_8") (pintype "bidirectional"))
      (node (ref "U4") (pin "12") (pinfunction "GPIO9_12") (pintype "bidirectional"))
    )
    (net (code "12") (name "DGND") (class "Default")
      (node (ref "C1") (pin "1") (pinfunction "1_1") (pintype "bidirectional"))
      (node (ref "C10") (pin "1") (pinfunction "1_1") (pintype "bidirectional"))
      (node (ref "C11") (pin "1") (pinfunction "1_1") (pintype "bidirectional"))
      (node (ref "C12") (pin "2") (pinfunction "2_2") (pintype "bidirectional"))
      (node (ref "C13") (pin "1") (pinfunction "1_1") (pintype "bidirectional"))
      (node (ref "C14") (pin "1") (pinfunction "1_1") (pintype "bidirectional"))
      (node (ref "C15") (pin "1") (pinfunction "1_1") (pintype "bidirectional"))
      (node (ref "C16") (pin "1") (pinfunction "1_1") (pintype "bidirectional"))
      (node (ref "C17") (pin "1") (pinfunction "1_1") (pintype "bidirectional"))
      (node (ref "C18") (pin "1") (pinfunction "1_1") (pintype "bidirectional"))
      (node (ref "C19") (pin "2") (pinfunction "2_2") (pintype "bidirectional"))
      (node (ref "C2") (pin "1") (pinfunction "1_1") (pintype "bidirectional"))
      (node (ref "C20") (pin "1") (pinfunction "1_1") (pintype "bidirectional"))
      (node (ref "C21") (pin "1") (pinfunction "1_1") (pintype "bidirectional"))
      (node (ref "C22") (pin "2") (pinfunction "2_2") (pintype "bidirectional"))
      (node (ref "C23") (pin "2") (pinfunction "2_2") (pintype "bidirectional"))
      (node (ref "C24") (pin "2") (pinfunction "2_2") (pintype "bidirectional"))
      (node (ref "C25") (pin "2") (pinfunction "2_2") (pintype "bidirectional"))
      (node (ref "C26") (pin "2") (pinfunction "2_2") (pintype "bidirectional"))
      (node (ref "C27") (pin "2") (pinfunction "2_2") (pintype "bidirectional"))
      (node (ref "C28") (pin "2") (pinfunction "2_2") (pintype "bidirectional"))
      (node (ref "C3") (pin "2") (pinfunction "2_2") (pintype "bidirectional"))
      (node (ref "C4") (pin "1") (pinfunction "1_1") (pintype "bidirectional"))
      (node (ref "C5") (pin "1") (pinfunction "1_1") (pintype "bidirectional"))
      (node (ref "C6") (pin "2") (pinfunction "2_2") (pintype "bidirectional"))
      (node (ref "C7") (pin "2") (pinfunction "2_2") (pintype "bidirectional"))
      (node (ref "C8") (pin "1") (pinfunction "1_1") (pintype "bidirectional"))
      (node (ref "C9") (pin "1") (pinfunction "1_1") (pintype "bidirectional"))
      (node (ref "J1") (pin "A1/B12") (pinfunction "GND_A1/B12") (pintype "power_in"))
      (node (ref "J1") (pin "B1/A12") (pinfunction "GND_B1/A12") (pintype "power_in"))
      (node (ref "J100") (pin "3") (pinfunction "GND_3") (pintype "bidirectional"))
      (node (ref "J100") (pin "5") (pinfunction "GND_5") (pintype "bidirectional"))
      (node (ref "J100") (pin "9") (pinfunction "GND_9") (pintype "bidirectional"))
      (node (ref "J2") (pin "1") (pinfunction "1_1") (pintype "bidirectional"))
      (node (ref "J3") (pin "2") (pinfunction "2_2") (pintype "bidirectional"))
      (node (ref "J3") (pin "4") (pinfunction "4_4") (pintype "bidirectional"))
      (node (ref "J4") (pin "1") (pinfunction "1_1") (pintype "bidirectional"))
      (node (ref "P1") (pin "1") (pinfunction "1_1") (pintype "bidirectional"))
      (node (ref "Q1") (pin "2") (pinfunction "S_2") (pintype "passive"))
      (node (ref "Q2") (pin "2") (pinfunction "EMITTER_2") (pintype "bidirectional"))
      (node (ref "Q3") (pin "3") (pinfunction "EMITTER_3") (pintype "bidirectional"))
      (node (ref "Q4") (pin "2") (pinfunction "EMITTER_2") (pintype "bidirectional"))
      (node (ref "Q5") (pin "2") (pinfunction "EMITTER_2") (pintype "bidirectional"))
      (node (ref "Q6") (pin "3") (pinfunction "EMITTER_3") (pintype "bidirectional"))
      (node (ref "Q7") (pin "2") (pinfunction "EMITTER_2") (pintype "bidirectional"))
      (node (ref "Q8") (pin "2") (pinfunction "EMITTER_2") (pintype "bidirectional"))
      (node (ref "Q9") (pin "3") (pinfunction "EMITTER_3") (pintype "bidirectional"))
      (node (ref "R1") (pin "2") (pinfunction "P$2_2") (pintype "bidirectional"))
      (node (ref "R2") (pin "1") (pinfunction "1A_1") (pintype "bidirectional"))
      (node (ref "R2") (pin "2") (pinfunction "2A_2") (pintype "bidirectional"))
      (node (ref "R2") (pin "3") (pinfunction "3A_3") (pintype "bidirectional"))
      (node (ref "R2") (pin "4") (pinfunction "4A_4") (pintype "bidirectional"))
      (node (ref "R9") (pin "1") (pinfunction "1A_1") (pintype "bidirectional"))
      (node (ref "R9") (pin "2") (pinfunction "2A_2") (pintype "bidirectional"))
      (node (ref "R9") (pin "3") (pinfunction "3A_3") (pintype "bidirectional"))
      (node (ref "R9") (pin "4") (pinfunction "4A_4") (pintype "bidirectional"))
      (node (ref "TP10") (pin "1") (pinfunction "TP_1") (pintype "bidirectional"))
      (node (ref "TP11") (pin "1") (pinfunction "TP_1") (pintype "bidirectional"))
      (node (ref "TP12") (pin "1") (pinfunction "TP_1") (pintype "bidirectional"))
      (node (ref "TP13") (pin "1") (pinfunction "TP_1") (pintype "bidirectional"))
      (node (ref "TP2") (pin "1") (pinfunction "TP_1") (pintype "bidirectional"))
      (node (ref "TP3") (pin "1") (pinfunction "TP_1") (pintype "bidirectional"))
      (node (ref "TP7") (pin "1") (pinfunction "TP_1") (pintype "bidirectional"))
      (node (ref "TP8") (pin "1") (pinfunction "TP_1") (pintype "bidirectional"))
      (node (ref "TP9") (pin "1") (pinfunction "TP_1") (pintype "bidirectional"))
      (node (ref "U1") (pin "1") (pinfunction "~{EN}_1") (pintype "bidirectional"))
      (node (ref "U1") (pin "2") (pinfunction "GND_2") (pintype "bidirectional"))
      (node (ref "U1") (pin "GND@PAD") (pinfunction "GND_GND@PAD") (pintype "bidirectional"))
      (node (ref "U2") (pin "2") (pinfunction "GND_2") (pintype "passive"))
      (node (ref "U3") (pin "2") (pinfunction "GND_2") (pintype "bidirectional"))
      (node (ref "U4") (pin "19") (pinfunction "TESTEN_19") (pintype "bidirectional"))
      (node (ref "U4") (pin "GND") (pinfunction "GND_GND") (pintype "bidirectional"))
      (node (ref "U5") (pin "4") (pinfunction "GND_4") (pintype "bidirectional"))
      (node (ref "U5") (pin "9") (pinfunction "GND_9") (pintype "bidirectional"))
      (node (ref "U7") (pin "2") (pinfunction "GND_2") (pintype "bidirectional"))
      (node (ref "U8") (pin "2") (pinfunction "GND_2") (pintype "bidirectional"))
      (node (ref "U9") (pin "2") (pinfunction "GND_2") (pintype "passive"))
    )
    (net (code "13") (name "EXT0") (class "Default")
      (node (ref "R10") (pin "8") (pinfunction "1B_8") (pintype "bidirectional"))
      (node (ref "U4") (pin "13") (pinfunction "GPIO10_13") (pintype "bidirectional"))
    )
    (net (code "14") (name "EXT1") (class "Default")
      (node (ref "R10") (pin "7") (pinfunction "2B_7") (pintype "bidirectional"))
      (node (ref "U4") (pin "14") (pinfunction "GPIO11_14") (pintype "bidirectional"))
    )
    (net (code "15") (name "EXT2") (class "Default")
      (node (ref "R10") (pin "6") (pinfunction "3B_6") (pintype "bidirectional"))
      (node (ref "U4") (pin "15") (pinfunction "GPIO12_15") (pintype "bidirectional"))
    )
    (net (code "16") (name "GPIO13") (class "Default")
      (node (ref "TP6") (pin "1") (pinfunction "TP_1") (pintype "bidirectional"))
      (node (ref "U4") (pin "16") (pinfunction "GPIO13_16") (pintype "bidirectional"))
    )
    (net (code "17") (name "GPIO14") (class "Default")
      (node (ref "TP5") (pin "1") (pinfunction "TP_1") (pintype "bidirectional"))
      (node (ref "U4") (pin "17") (pinfunction "GPIO14_17") (pintype "bidirectional"))
    )
    (net (code "18") (name "GPIO15") (class "Default")
      (node (ref "TP4") (pin "1") (pinfunction "TP_1") (pintype "bidirectional"))
      (node (ref "U4") (pin "18") (pinfunction "GPIO15_18") (pintype "bidirectional"))
    )
    (net (code "19") (name "GPIO28") (class "Default")
      (node (ref "TP1") (pin "1") (pinfunction "TP_1") (pintype "bidirectional"))
      (node (ref "U4") (pin "40") (pinfunction "GPIO28_ADC2_40") (pintype "bidirectional"))
    )
    (net (code "20") (name "I+") (class "Default")
      (node (ref "C23") (pin "1") (pinfunction "1_1") (pintype "bidirectional"))
      (node (ref "C24") (pin "1") (pinfunction "1_1") (pintype "bidirectional"))
      (node (ref "C26") (pin "1") (pinfunction "1_1") (pintype "bidirectional"))
      (node (ref "C27") (pin "1") (pinfunction "1_1") (pintype "bidirectional"))
      (node (ref "C28") (pin "1") (pinfunction "1_1") (pintype "bidirectional"))
      (node (ref "L1") (pin "2") (pinfunction "P$2_2") (pintype "bidirectional"))
      (node (ref "P2") (pin "1") (pinfunction "1_1") (pintype "bidirectional"))
      (node (ref "P3") (pin "1") (pinfunction "1_1") (pintype "bidirectional"))
      (node (ref "R14") (pin "2") (pinfunction "P$2_2") (pintype "bidirectional"))
      (node (ref "R20") (pin "2") (pinfunction "P$2_2") (pintype "bidirectional"))
      (node (ref "U8") (pin "5") (pinfunction "OUT_5") (pintype "bidirectional"))
    )
    (net (code "21") (name "I-") (class "Default")
      (node (ref "C29") (pin "2") (pinfunction "2_2") (pintype "bidirectional"))
      (node (ref "C30") (pin "1") (pinfunction "1_1") (pintype "bidirectional"))
      (node (ref "J4") (pin "2") (pinfunction "2_2") (pintype "bidirectional"))
      (node (ref "P4") (pin "1") (pinfunction "1_1") (pintype "bidirectional"))
      (node (ref "R21") (pin "2") (pinfunction "P$2_2") (pintype "bidirectional"))
      (node (ref "R22") (pin "2") (pinfunction "P$2_2") (pintype "bidirectional"))
      (node (ref "R23") (pin "2") (pinfunction "P$2_2") (pintype "bidirectional"))
      (node (ref "R24") (pin "2") (pinfunction "P$2_2") (pintype "bidirectional"))
      (node (ref "R25") (pin "2") (pinfunction "P$2_2") (pintype "bidirectional"))
      (node (ref "R26") (pin "2") (pinfunction "P$2_2") (pintype "bidirectional"))
      (node (ref "R27") (pin "2") (pinfunction "P$2_2") (pintype "bidirectional"))
      (node (ref "R28") (pin "2") (pinfunction "P$2_2") (pintype "bidirectional"))
    )
    (net (code "22") (name "LDO_EN") (class "Default")
      (node (ref "R9") (pin "6") (pinfunction "3B_6") (pintype "bidirectional"))
      (node (ref "U4") (pin "30") (pinfunction "GPIO19_30") (pintype "bidirectional"))
      (node (ref "U8") (pin "3") (pinfunction "EN_3") (pintype "bidirectional"))
    )
    (net (code "23") (name "LDO_FB") (class "Default")
      (node (ref "R19") (pin "2") (pinfunction "P$2_2") (pintype "bidirectional"))
      (node (ref "R20") (pin "1") (pinfunction "P$1_1") (pintype "bidirectional"))
      (node (ref "U8") (pin "4") (pinfunction "ADJ_4") (pintype "bidirectional"))
    )
    (net (code "24") (name "LED_B") (class "Default")
      (node (ref "R7") (pin "5") (pinfunction "4B_5") (pintype "bidirectional"))
      (node (ref "U4") (pin "27") (pinfunction "GPIO16_27") (pintype "bidirectional"))
    )
    (net (code "25") (name "LED_G") (class "Default")
      (node (ref "R7") (pin "7") (pinfunction "2B_7") (pintype "bidirectional"))
      (node (ref "U4") (pin "29") (pinfunction "GPIO18_29") (pintype "bidirectional"))
    )
    (net (code "26") (name "LED_R") (class "Default")
      (node (ref "R7") (pin "6") (pinfunction "3B_6") (pintype "bidirectional"))
      (node (ref "U4") (pin "28") (pinfunction "GPIO17_28") (pintype "bidirectional"))
    )
    (net (code "27") (name "Net-(R8-P$1)") (class "Default")
      (node (ref "J2") (pin "2") (pinfunction "2_2") (pintype "bidirectional"))
      (node (ref "R8") (pin "1") (pinfunction "P$1_1") (pintype "bidirectional"))
    )
    (net (code "28") (name "QSPI_SCLK") (class "Default")
      (node (ref "U4") (pin "52") (pinfunction "QSPI_SCLK_52") (pintype "bidirectional"))
      (node (ref "U5") (pin "6") (pinfunction "SCK_6") (pintype "bidirectional"))
    )
    (net (code "29") (name "QSPI_SD0") (class "Default")
      (node (ref "U4") (pin "53") (pinfunction "QSPI_SD0_53") (pintype "bidirectional"))
      (node (ref "U5") (pin "5") (pinfunction "SI(D0)_5") (pintype "bidirectional"))
    )
    (net (code "30") (name "QSPI_SD1") (class "Default")
      (node (ref "U4") (pin "55") (pinfunction "QSPI_SD1_55") (pintype "bidirectional"))
      (node (ref "U5") (pin "2") (pinfunction "SO(D1)_2") (pintype "bidirectional"))
    )
    (net (code "31") (name "QSPI_SD2") (class "Default")
      (node (ref "U4") (pin "54") (pinfunction "QSPI_SD2_54") (pintype "bidirectional"))
      (node (ref "U5") (pin "3") (pinfunction "~{WP}(D2)_3") (pintype "bidirectional"))
    )
    (net (code "32") (name "QSPI_SD3") (class "Default")
      (node (ref "U4") (pin "51") (pinfunction "QSPI_SD3_51") (pintype "bidirectional"))
      (node (ref "U5") (pin "7") (pinfunction "~{HOLD}(D3)_7") (pintype "bidirectional"))
    )
    (net (code "33") (name "RT_1") (class "Default")
      (node (ref "Q3") (pin "2") (pinfunction "COLLECTOR_2") (pintype "bidirectional"))
      (node (ref "R23") (pin "1") (pinfunction "P$1_1") (pintype "bidirectional"))
    )
    (net (code "34") (name "RT_1K") (class "Default")
      (node (ref "Q8") (pin "3") (pinfunction "COLLECTOR_3") (pintype "bidirectional"))
      (node (ref "R28") (pin "1") (pinfunction "P$1_1") (pintype "bidirectional"))
    )
    (net (code "35") (name "RT_1M") (class "Default")
      (node (ref "Q4") (pin "3") (pinfunction "COLLECTOR_3") (pintype "bidirectional"))
      (node (ref "R22") (pin "1") (pinfunction "P$1_1") (pintype "bidirectional"))
    )
    (net (code "36") (name "RT_10") (class "Default")
      (node (ref "Q6") (pin "2") (pinfunction "COLLECTOR_2") (pintype "bidirectional"))
      (node (ref "R25") (pin "1") (pinfunction "P$1_1") (pintype "bidirectional"))
    )
    (net (code "37") (name "RT_10K") (class "Default")
      (node (ref "Q7") (pin "3") (pinfunction "COLLECTOR_3") (pintype "bidirectional"))
      (node (ref "R26") (pin "1") (pinfunction "P$1_1") (pintype "bidirectional"))
    )
    (net (code "38") (name "RT_10M") (class "Default")
      (node (ref "Q2") (pin "3") (pinfunction "COLLECTOR_3") (pintype "bidirectional"))
      (node (ref "R21") (pin "1") (pinfunction "P$1_1") (pintype "bidirectional"))
    )
    (net (code "39") (name "RT_100") (class "Default")
      (node (ref "Q9") (pin "2") (pinfunction "COLLECTOR_2") (pintype "bidirectional"))
      (node (ref "R27") (pin "1") (pinfunction "P$1_1") (pintype "bidirectional"))
    )
    (net (code "40") (name "RT_100K") (class "Default")
      (node (ref "Q5") (pin "3") (pinfunction "COLLECTOR_3") (pintype "bidirectional"))
      (node (ref "R24") (pin "1") (pinfunction "P$1_1") (pintype "bidirectional"))
    )
    (net (code "41") (name "R_1") (class "Default")
      (node (ref "R16") (pin "5") (pinfunction "4B_5") (pintype "bidirectional"))
      (node (ref "U4") (pin "2") (pinfunction "GPIO0_2") (pintype "bidirectional"))
    )
    (net (code "42") (name "R_1K") (class "Default")
      (node (ref "R17") (pin "7") (pinfunction "2B_7") (pintype "bidirectional"))
      (node (ref "U4") (pin "5") (pinfunction "GPIO3_5") (pintype "bidirectional"))
    )
    (net (code "43") (name "R_1M") (class "Default")
      (node (ref "R15") (pin "6") (pinfunction "3B_6") (pintype "bidirectional"))
      (node (ref "U4") (pin "8") (pinfunction "GPIO6_8") (pintype "bidirectional"))
    )
    (net (code "44") (name "R_10") (class "Default")
      (node (ref "R17") (pin "5") (pinfunction "4B_5") (pintype "bidirectional"))
      (node (ref "U4") (pin "3") (pinfunction "GPIO1_3") (pintype "bidirectional"))
    )
    (net (code "45") (name "R_10K") (class "Default")
      (node (ref "R17") (pin "8") (pinfunction "1B_8") (pintype "bidirectional"))
      (node (ref "U4") (pin "6") (pinfunction "GPIO4_6") (pintype "bidirectional"))
    )
    (net (code "46") (name "R_10M") (class "Default")
      (node (ref "R15") (pin "7") (pinfunction "2B_7") (pintype "bidirectional"))
      (node (ref "U4") (pin "9") (pinfunction "GPIO7_9") (pintype "bidirectional"))
    )
    (net (code "47") (name "R_100") (class "Default")
      (node (ref "R17") (pin "6") (pinfunction "3B_6") (pintype "bidirectional"))
      (node (ref "U4") (pin "4") (pinfunction "GPIO2_4") (pintype "bidirectional"))
    )
    (net (code "48") (name "R_100K") (class "Default")
      (node (ref "R15") (pin "5") (pinfunction "4B_5") (pintype "bidirectional"))
      (node (ref "U4") (pin "7") (pinfunction "GPIO5_7") (pintype "bidirectional"))
    )
    (net (code "49") (name "SWDCLK") (class "Default")
      (node (ref "J100") (pin "4") (pinfunction "SWDCLK_4") (pintype "bidirectional"))
      (node (ref "U4") (pin "24") (pinfunction "SWCLK_24") (pintype "bidirectional"))
    )
    (net (code "50") (name "SWDIO") (class "Default")
      (node (ref "J100") (pin "2") (pinfunction "SWDIO_2") (pintype "bidirectional"))
      (node (ref "U4") (pin "25") (pinfunction "SWDIO_25") (pintype "bidirectional"))
    )
    (net (code "51") (name "TC_10UF") (class "Default")
      (node (ref "Q1") (pin "1") (pinfunction "G_1") (pintype "passive"))
      (node (ref "R16") (pin "3") (pinfunction "3A_3") (pintype "bidirectional"))
    )
    (net (code "52") (name "TC_PWM") (class "Default")
      (node (ref "C29") (pin "1") (pinfunction "1_1") (pintype "bidirectional"))
      (node (ref "R15") (pin "1") (pinfunction "1A_1") (pintype "bidirectional"))
    )
    (net (code "53") (name "TLED_B") (class "Default")
      (node (ref "R7") (pin "4") (pinfunction "4A_4") (pintype "bidirectional"))
      (node (ref "U6") (pin "5") (pinfunction "BLUE_CATHODE-_5") (pintype "passive"))
    )
    (net (code "54") (name "TLED_G") (class "Default")
      (node (ref "R7") (pin "2") (pinfunction "2A_2") (pintype "bidirectional"))
      (node (ref "U6") (pin "1") (pinfunction "GREEN_CATHODE-_1") (pintype "passive"))
    )
    (net (code "55") (name "TLED_R") (class "Default")
      (node (ref "R7") (pin "3") (pinfunction "3A_3") (pintype "bidirectional"))
      (node (ref "U6") (pin "3") (pinfunction "RED_CATHODE-_3") (pintype "passive"))
    )
    (net (code "56") (name "TR_1") (class "Default")
      (node (ref "Q3") (pin "1") (pinfunction "BASE_1") (pintype "bidirectional"))
      (node (ref "R16") (pin "4") (pinfunction "4A_4") (pintype "bidirectional"))
    )
    (net (code "57") (name "TR_1K") (class "Default")
      (node (ref "Q8") (pin "1") (pinfunction "BASE_1") (pintype "bidirectional"))
      (node (ref "R17") (pin "2") (pinfunction "2A_2") (pintype "bidirectional"))
    )
    (net (code "58") (name "TR_1M") (class "Default")
      (node (ref "Q4") (pin "1") (pinfunction "BASE_1") (pintype "bidirectional"))
      (node (ref "R15") (pin "3") (pinfunction "3A_3") (pintype "bidirectional"))
    )
    (net (code "59") (name "TR_10") (class "Default")
      (node (ref "Q6") (pin "1") (pinfunction "BASE_1") (pintype "bidirectional"))
      (node (ref "R17") (pin "4") (pinfunction "4A_4") (pintype "bidirectional"))
    )
    (net (code "60") (name "TR_10K") (class "Default")
      (node (ref "Q7") (pin "1") (pinfunction "BASE_1") (pintype "bidirectional"))
      (node (ref "R17") (pin "1") (pinfunction "1A_1") (pintype "bidirectional"))
    )
    (net (code "61") (name "TR_10M") (class "Default")
      (node (ref "Q2") (pin "1") (pinfunction "BASE_1") (pintype "bidirectional"))
      (node (ref "R15") (pin "2") (pinfunction "2A_2") (pintype "bidirectional"))
    )
    (net (code "62") (name "TR_100") (class "Default")
      (node (ref "Q9") (pin "1") (pinfunction "BASE_1") (pintype "bidirectional"))
      (node (ref "R17") (pin "3") (pinfunction "3A_3") (pintype "bidirectional"))
    )
    (net (code "63") (name "TR_100K") (class "Default")
      (node (ref "Q5") (pin "1") (pinfunction "BASE_1") (pintype "bidirectional"))
      (node (ref "R15") (pin "4") (pinfunction "4A_4") (pintype "bidirectional"))
    )
    (net (code "64") (name "UART1_RX") (class "Default")
      (node (ref "J100") (pin "7") (pinfunction "DBG_TX/KEY_7") (pintype "bidirectional"))
      (node (ref "U4") (pin "37") (pinfunction "GPIO25_37") (pintype "bidirectional"))
    )
    (net (code "65") (name "UART1_TX") (class "Default")
      (node (ref "J100") (pin "8") (pinfunction "DBG_RX/NC_8") (pintype "bidirectional"))
      (node (ref "U4") (pin "36") (pinfunction "GPIO24_36") (pintype "bidirectional"))
    )
    (net (code "66") (name "USB_DTM") (class "Default")
      (node (ref "R3") (pin "2") (pinfunction "P$2_2") (pintype "bidirectional"))
      (node (ref "U4") (pin "46") (pinfunction "USB_DM_46") (pintype "bidirectional"))
    )
    (net (code "67") (name "USB_DTP") (class "Default")
      (node (ref "R4") (pin "2") (pinfunction "P$2_2") (pintype "bidirectional"))
      (node (ref "U4") (pin "47") (pinfunction "USB_DP_47") (pintype "bidirectional"))
    )
    (net (code "68") (name "USB_N") (class "Default")
      (node (ref "J1") (pin "A7") (pinfunction "DN1_A7") (pintype "bidirectional"))
      (node (ref "J1") (pin "B7") (pinfunction "DN2_B7") (pintype "bidirectional"))
      (node (ref "R3") (pin "1") (pinfunction "P$1_1") (pintype "bidirectional"))
      (node (ref "U2") (pin "6") (pinfunction "D1-_6") (pintype "passive"))
    )
    (net (code "69") (name "USB_P") (class "Default")
      (node (ref "J1") (pin "A6") (pinfunction "DP1_A6") (pintype "bidirectional"))
      (node (ref "J1") (pin "B6") (pinfunction "DP2_B6") (pintype "bidirectional"))
      (node (ref "R4") (pin "1") (pinfunction "P$1_1") (pintype "bidirectional"))
      (node (ref "U2") (pin "1") (pinfunction "D1+_1") (pintype "passive"))
    )
    (net (code "70") (name "USB_V") (class "Default")
      (node (ref "C1") (pin "2") (pinfunction "2_2") (pintype "bidirectional"))
      (node (ref "C5") (pin "2") (pinfunction "2_2") (pintype "bidirectional"))
      (node (ref "J1") (pin "A4/B9") (pinfunction "VBUS_A4/B9") (pintype "power_in"))
      (node (ref "J1") (pin "B4/A9") (pinfunction "VBUS_B4/A9") (pintype "power_in"))
      (node (ref "U1") (pin "3") (pinfunction "IN_3") (pintype "bidirectional"))
    )
    (net (code "71") (name "VIN") (class "Default")
      (node (ref "C22") (pin "1") (pinfunction "1_1") (pintype "bidirectional"))
      (node (ref "C25") (pin "1") (pinfunction "1_1") (pintype "bidirectional"))
      (node (ref "C6") (pin "1") (pinfunction "1_1") (pintype "bidirectional"))
      (node (ref "FB1") (pin "2") (pinfunction "2_2") (pintype "bidirectional"))
      (node (ref "U3") (pin "1") (pinfunction "IN_1") (pintype "bidirectional"))
      (node (ref "U3") (pin "3") (pinfunction "EN_3") (pintype "bidirectional"))
      (node (ref "U7") (pin "4") (pinfunction "IN_4") (pintype "bidirectional"))
      (node (ref "U8") (pin "1") (pinfunction "IN_1") (pintype "bidirectional"))
    )
    (net (code "72") (name "VIN_F") (class "Default")
      (node (ref "C2") (pin "2") (pinfunction "2_2") (pintype "bidirectional"))
      (node (ref "C4") (pin "2") (pinfunction "2_2") (pintype "bidirectional"))
      (node (ref "FB1") (pin "1") (pinfunction "1_1") (pintype "bidirectional"))
      (node (ref "U1") (pin "4") (pinfunction "OUT_4") (pintype "bidirectional"))
      (node (ref "U1") (pin "5") (pinfunction "OUT_5") (pintype "bidirectional"))
    )
    (net (code "73") (name "VSET_BUCK_1V0") (class "Default")
      (node (ref "R11") (pin "1") (pinfunction "P$1_1") (pintype "bidirectional"))
      (node (ref "U4") (pin "32") (pinfunction "GPIO21_32") (pintype "bidirectional"))
    )
    (net (code "74") (name "VSET_BUCK_1V8") (class "Default")
      (node (ref "R11") (pin "2") (pinfunction "P$2_2") (pintype "bidirectional"))
      (node (ref "R12") (pin "1") (pinfunction "P$1_1") (pintype "bidirectional"))
      (node (ref "U4") (pin "34") (pinfunction "GPIO22_34") (pintype "bidirectional"))
    )
    (net (code "75") (name "VSET_BUCK_3V3") (class "Default")
      (node (ref "R12") (pin "2") (pinfunction "P$2_2") (pintype "bidirectional"))
      (node (ref "R13") (pin "1") (pinfunction "P$1_1") (pintype "bidirectional"))
      (node (ref "U4") (pin "35") (pinfunction "GPIO23_35") (pintype "bidirectional"))
    )
    (net (code "76") (name "VSET_LDO_1V8") (class "Default")
      (node (ref "R18") (pin "1") (pinfunction "P$1_1") (pintype "bidirectional"))
      (node (ref "U4") (pin "38") (pinfunction "GPIO26_ADC0_38") (pintype "bidirectional"))
    )
    (net (code "77") (name "VSET_LDO_3V3") (class "Default")
      (node (ref "R18") (pin "2") (pinfunction "P$2_2") (pintype "bidirectional"))
      (node (ref "R19") (pin "1") (pinfunction "P$1_1") (pintype "bidirectional"))
      (node (ref "U4") (pin "39") (pinfunction "GPIO27_ADC1_39") (pintype "bidirectional"))
    )
    (net (code "78") (name "X0") (class "Default")
      (node (ref "J3") (pin "1") (pinfunction "1_1") (pintype "bidirectional"))
      (node (ref "R10") (pin "1") (pinfunction "1A_1") (pintype "bidirectional"))
      (node (ref "U9") (pin "4") (pinfunction "D2-_4") (pintype "passive"))
    )
    (net (code "79") (name "X1") (class "Default")
      (node (ref "J3") (pin "3") (pinfunction "3_3") (pintype "bidirectional"))
      (node (ref "R10") (pin "2") (pinfunction "2A_2") (pintype "bidirectional"))
      (node (ref "U9") (pin "6") (pinfunction "D1-_6") (pintype "passive"))
    )
    (net (code "80") (name "X2") (class "Default")
      (node (ref "J3") (pin "5") (pinfunction "5_5") (pintype "bidirectional"))
      (node (ref "R10") (pin "3") (pinfunction "3A_3") (pintype "bidirectional"))
      (node (ref "U9") (pin "1") (pinfunction "D1+_1") (pintype "passive"))
    )
    (net (code "81") (name "XIN") (class "Default")
      (node (ref "C19") (pin "1") (pinfunction "1_1") (pintype "bidirectional"))
      (node (ref "U4") (pin "20") (pinfunction "XIN_20") (pintype "bidirectional"))
      (node (ref "X1") (pin "3") (pinfunction "2_3") (pintype "passive"))
    )
    (net (code "82") (name "XOUT") (class "Default")
      (node (ref "R5") (pin "2") (pinfunction "P$2_2") (pintype "bidirectional"))
      (node (ref "U4") (pin "21") (pinfunction "XOUT_21") (pintype "bidirectional"))
    )
    (net (code "83") (name "XOUT_R") (class "Default")
      (node (ref "C12") (pin "1") (pinfunction "1_1") (pintype "bidirectional"))
      (node (ref "R5") (pin "1") (pinfunction "P$1_1") (pintype "bidirectional"))
      (node (ref "X1") (pin "1") (pinfunction "1_1") (pintype "passive"))
    )
    (net (code "84") (name "unconnected-(J1-SBU1-PadA8)") (class "Default")
      (node (ref "J1") (pin "A8") (pinfunction "SBU1_A8") (pintype "bidirectional"))
    )
    (net (code "85") (name "unconnected-(J1-SBU2-PadB8)") (class "Default")
      (node (ref "J1") (pin "B8") (pinfunction "SBU2_B8") (pintype "bidirectional"))
    )
    (net (code "86") (name "unconnected-(J100-SWO-Pad6)") (class "Default")
      (node (ref "J100") (pin "6") (pinfunction "SWO_6") (pintype "bidirectional"))
    )
    (net (code "87") (name "unconnected-(R2-3B-Pad6)") (class "Default")
      (node (ref "R2") (pin "6") (pinfunction "3B_6") (pintype "bidirectional"))
    )
    (net (code "88") (name "unconnected-(R2-4B-Pad5)") (class "Default")
      (node (ref "R2") (pin "5") (pinfunction "4B_5") (pintype "bidirectional"))
    )
    (net (code "89") (name "unconnected-(R7-1A-Pad1)") (class "Default")
      (node (ref "R7") (pin "1") (pinfunction "1A_1") (pintype "bidirectional"))
    )
    (net (code "90") (name "unconnected-(R7-1B-Pad8)") (class "Default")
      (node (ref "R7") (pin "8") (pinfunction "1B_8") (pintype "bidirectional"))
    )
    (net (code "91") (name "unconnected-(R9-1B-Pad8)") (class "Default")
      (node (ref "R9") (pin "8") (pinfunction "1B_8") (pintype "bidirectional"))
    )
    (net (code "92") (name "unconnected-(R9-2B-Pad7)") (class "Default")
      (node (ref "R9") (pin "7") (pinfunction "2B_7") (pintype "bidirectional"))
    )
    (net (code "93") (name "unconnected-(R10-4A-Pad4)") (class "Default")
      (node (ref "R10") (pin "4") (pinfunction "4A_4") (pintype "bidirectional"))
    )
    (net (code "94") (name "unconnected-(R10-4B-Pad5)") (class "Default")
      (node (ref "R10") (pin "5") (pinfunction "4B_5") (pintype "bidirectional"))
    )
    (net (code "95") (name "unconnected-(R16-1A-Pad1)") (class "Default")
      (node (ref "R16") (pin "1") (pinfunction "1A_1") (pintype "bidirectional"))
    )
    (net (code "96") (name "unconnected-(R16-1B-Pad8)") (class "Default")
      (node (ref "R16") (pin "8") (pinfunction "1B_8") (pintype "bidirectional"))
    )
    (net (code "97") (name "unconnected-(R16-2A-Pad2)") (class "Default")
      (node (ref "R16") (pin "2") (pinfunction "2A_2") (pintype "bidirectional"))
    )
    (net (code "98") (name "unconnected-(R16-2B-Pad7)") (class "Default")
      (node (ref "R16") (pin "7") (pinfunction "2B_7") (pintype "bidirectional"))
    )
    (net (code "99") (name "unconnected-(U1-~{FLAG}-Pad6)") (class "Default")
      (node (ref "U1") (pin "6") (pinfunction "~{FLAG}_6") (pintype "bidirectional"))
    )
    (net (code "100") (name "unconnected-(U2-D2+-Pad3)") (class "Default")
      (node (ref "U2") (pin "3") (pinfunction "D2+_3") (pintype "passive"))
    )
    (net (code "101") (name "unconnected-(U2-D2--Pad4)") (class "Default")
      (node (ref "U2") (pin "4") (pinfunction "D2-_4") (pintype "passive"))
    )
    (net (code "102") (name "unconnected-(U4-GPIO29_ADC3-Pad41)") (class "Default")
      (node (ref "U4") (pin "41") (pinfunction "GPIO29_ADC3_41") (pintype "bidirectional"))
    )
    (net (code "103") (name "unconnected-(U9-D2+-Pad3)") (class "Default")
      (node (ref "U9") (pin "3") (pinfunction "D2+_3") (pintype "passive"))
    )
    (net (code "104") (name "~{QSPI_CS}") (class "Default")
      (node (ref "R6") (pin "1") (pinfunction "P$1_1") (pintype "bidirectional"))
      (node (ref "R8") (pin "2") (pinfunction "P$2_2") (pintype "bidirectional"))
      (node (ref "U4") (pin "56") (pinfunction "QSPI_SS_N_56") (pintype "bidirectional"))
      (node (ref "U5") (pin "1") (pinfunction "~{CS}_1") (pintype "bidirectional"))
    )
    (net (code "105") (name "~{RESET}") (class "Default")
      (node (ref "J100") (pin "10") (pinfunction "~{RESET}_10") (pintype "bidirectional"))
      (node (ref "U4") (pin "26") (pinfunction "RUN_26") (pintype "bidirectional"))
    )
  )
)
